# catbit.net
KiCad netlist of a schematic drawn in EAGLE
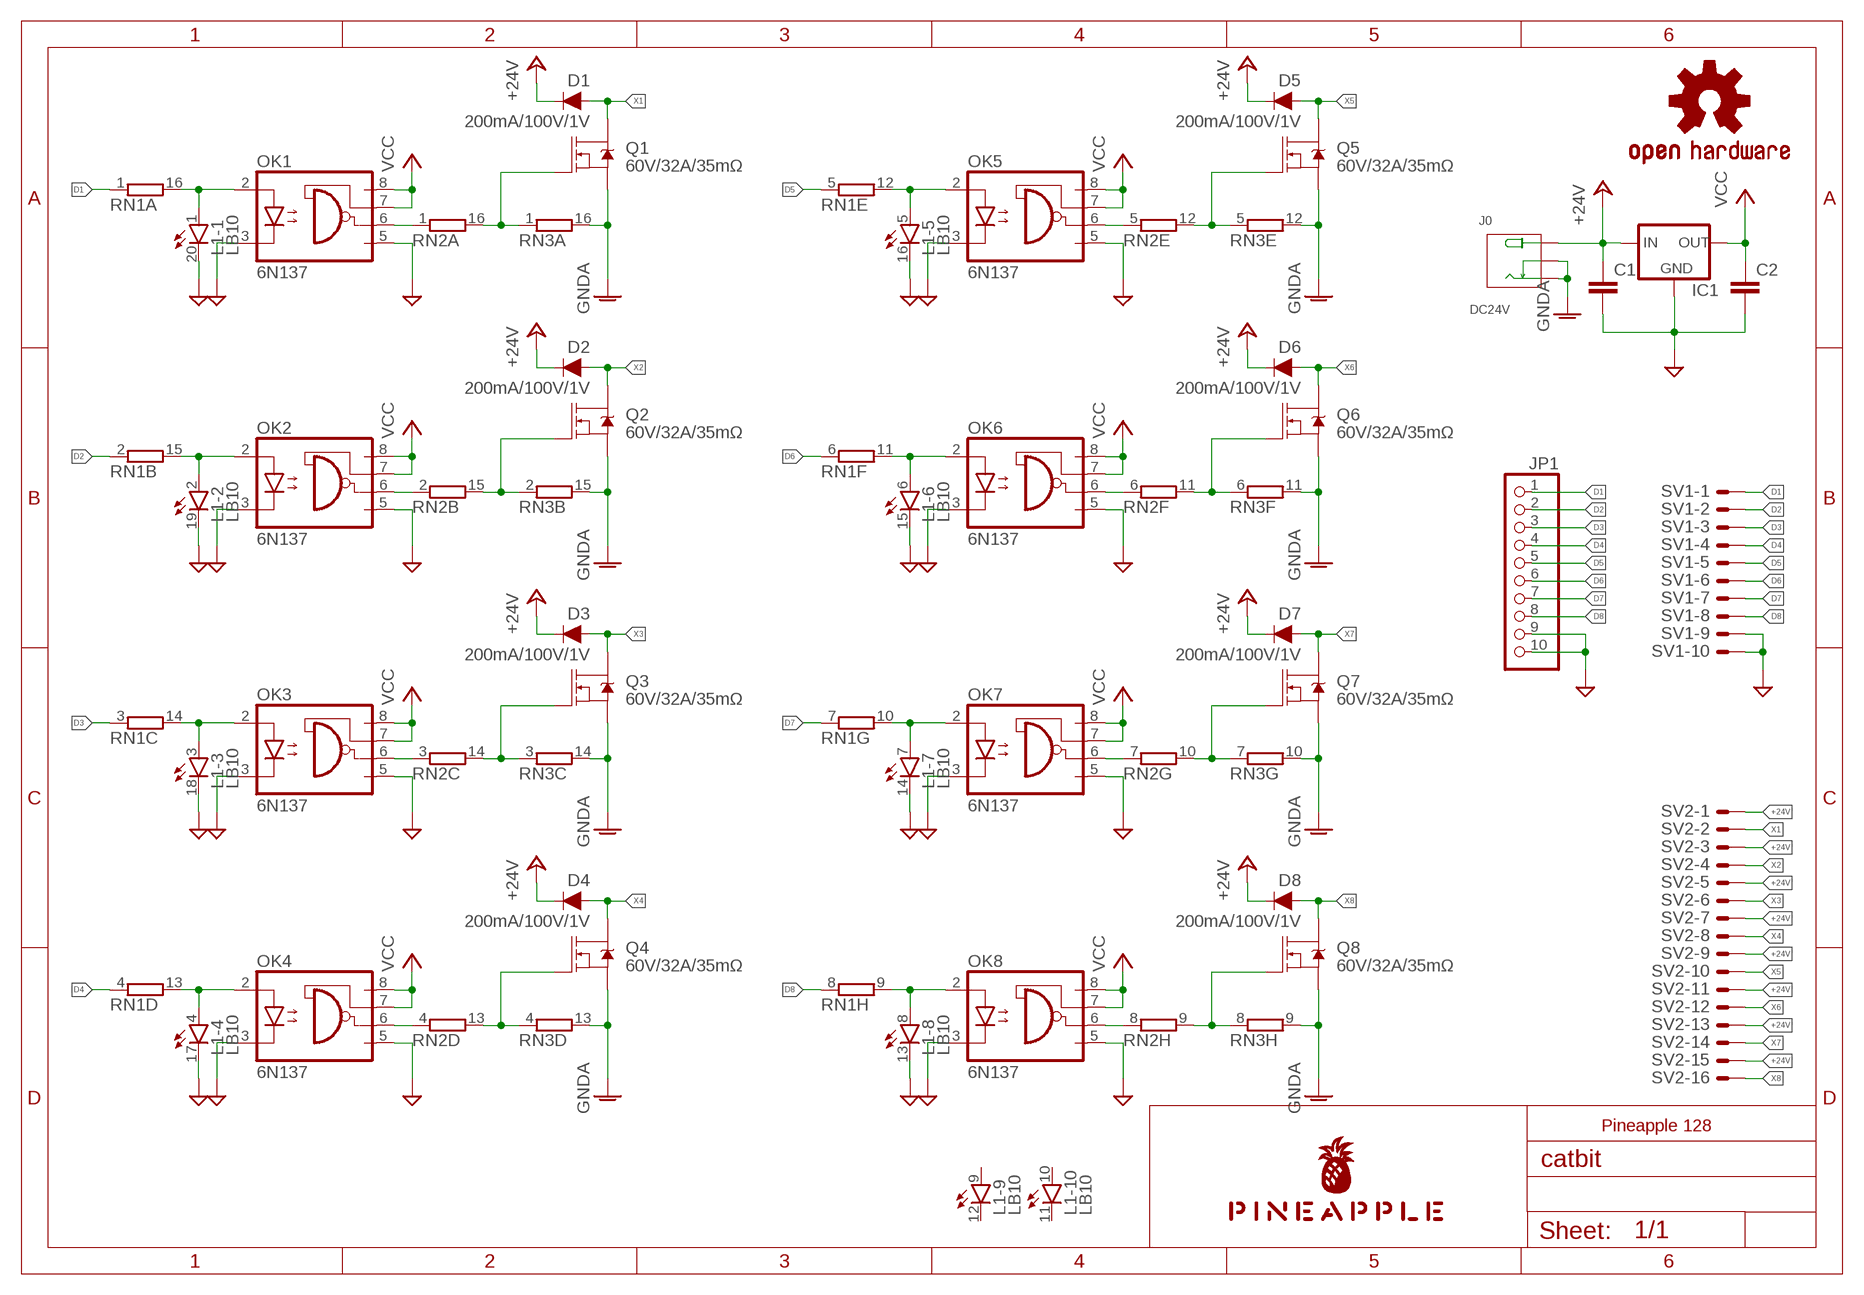
[diagram p0: schematic, sheet 1]

(export (version "E")
  (design (tool "Eeschema 10.0.6"))
  (components
    (comp (ref "C1")
      (value "C-EU025-024X044")
      (footprint "eagle-import:C025-024X044")
      (libsource (lib "eagle-import") (part "C-EU025-024X044"))
    )
    (comp (ref "C2")
      (value "C-EU025-024X044")
      (footprint "eagle-import:C025-024X044")
      (libsource (lib "eagle-import") (part "C-EU025-024X044"))
    )
    (comp (ref "D1")
      (value "200mA/100V/1V")
      (footprint "eagle-import:DIODE-1N4148")
      (libsource (lib "eagle-import") (part "DIODE-1N4148"))
    )
    (comp (ref "D2")
      (value "200mA/100V/1V")
      (footprint "eagle-import:DIODE-1N4148")
      (libsource (lib "eagle-import") (part "DIODE-1N4148"))
    )
    (comp (ref "D3")
      (value "200mA/100V/1V")
      (footprint "eagle-import:DIODE-1N4148")
      (libsource (lib "eagle-import") (part "DIODE-1N4148"))
    )
    (comp (ref "D4")
      (value "200mA/100V/1V")
      (footprint "eagle-import:DIODE-1N4148")
      (libsource (lib "eagle-import") (part "DIODE-1N4148"))
    )
    (comp (ref "D5")
      (value "200mA/100V/1V")
      (footprint "eagle-import:DIODE-1N4148")
      (libsource (lib "eagle-import") (part "DIODE-1N4148"))
    )
    (comp (ref "D6")
      (value "200mA/100V/1V")
      (footprint "eagle-import:DIODE-1N4148")
      (libsource (lib "eagle-import") (part "DIODE-1N4148"))
    )
    (comp (ref "D7")
      (value "200mA/100V/1V")
      (footprint "eagle-import:DIODE-1N4148")
      (libsource (lib "eagle-import") (part "DIODE-1N4148"))
    )
    (comp (ref "D8")
      (value "200mA/100V/1V")
      (footprint "eagle-import:DIODE-1N4148")
      (libsource (lib "eagle-import") (part "DIODE-1N4148"))
    )
    (comp (ref "IC1")
      (value "78XXS")
      (footprint "eagle-import:78XXS")
      (libsource (lib "eagle-import") (part "78XXS"))
    )
    (comp (ref "J0")
      (value "DC24V")
      (footprint "eagle-import:3P-L14.2_W11.0_H9.0MM")
      (libsource (lib "eagle-import") (part "JACK-DC-005'DC-005'"))
    )
    (comp (ref "JP1")
      (value "PINHD-1X10")
      (footprint "eagle-import:1X10")
      (libsource (lib "eagle-import") (part "PINHD-1X10"))
    )
    (comp (ref "L1")
      (value "LB10")
      (footprint "eagle-import:LB10")
      (libsource (lib "eagle-import") (part "LB10"))
    )
    (comp (ref "LOGO1")
      (value "OSHW-LOGOS-COPPER")
      (footprint "eagle-import:OSHW-LOGO-S_COPPER")
      (libsource (lib "eagle-import") (part "OSHW-LOGOS-COPPER"))
    )
    (comp (ref "OK1")
      (value "6N137")
      (footprint "eagle-import:DIL08")
      (libsource (lib "eagle-import") (part "6N137"))
    )
    (comp (ref "OK2")
      (value "6N137")
      (footprint "eagle-import:DIL08")
      (libsource (lib "eagle-import") (part "6N137"))
    )
    (comp (ref "OK3")
      (value "6N137")
      (footprint "eagle-import:DIL08")
      (libsource (lib "eagle-import") (part "6N137"))
    )
    (comp (ref "OK4")
      (value "6N137")
      (footprint "eagle-import:DIL08")
      (libsource (lib "eagle-import") (part "6N137"))
    )
    (comp (ref "OK5")
      (value "6N137")
      (footprint "eagle-import:DIL08")
      (libsource (lib "eagle-import") (part "6N137"))
    )
    (comp (ref "OK6")
      (value "6N137")
      (footprint "eagle-import:DIL08")
      (libsource (lib "eagle-import") (part "6N137"))
    )
    (comp (ref "OK7")
      (value "6N137")
      (footprint "eagle-import:DIL08")
      (libsource (lib "eagle-import") (part "6N137"))
    )
    (comp (ref "OK8")
      (value "6N137")
      (footprint "eagle-import:DIL08")
      (libsource (lib "eagle-import") (part "6N137"))
    )
    (comp (ref "Q1")
      (value "60V/32A/35mΩ")
      (footprint "eagle-import:TO220V")
      (libsource (lib "eagle-import") (part "MOSFET-NCH-FQP30N06L"))
    )
    (comp (ref "Q2")
      (value "60V/32A/35mΩ")
      (footprint "eagle-import:TO220V")
      (libsource (lib "eagle-import") (part "MOSFET-NCH-FQP30N06L"))
    )
    (comp (ref "Q3")
      (value "60V/32A/35mΩ")
      (footprint "eagle-import:TO220V")
      (libsource (lib "eagle-import") (part "MOSFET-NCH-FQP30N06L"))
    )
    (comp (ref "Q4")
      (value "60V/32A/35mΩ")
      (footprint "eagle-import:TO220V")
      (libsource (lib "eagle-import") (part "MOSFET-NCH-FQP30N06L"))
    )
    (comp (ref "Q5")
      (value "60V/32A/35mΩ")
      (footprint "eagle-import:TO220V")
      (libsource (lib "eagle-import") (part "MOSFET-NCH-FQP30N06L"))
    )
    (comp (ref "Q6")
      (value "60V/32A/35mΩ")
      (footprint "eagle-import:TO220V")
      (libsource (lib "eagle-import") (part "MOSFET-NCH-FQP30N06L"))
    )
    (comp (ref "Q7")
      (value "60V/32A/35mΩ")
      (footprint "eagle-import:TO220V")
      (libsource (lib "eagle-import") (part "MOSFET-NCH-FQP30N06L"))
    )
    (comp (ref "Q8")
      (value "60V/32A/35mΩ")
      (footprint "eagle-import:TO220V")
      (libsource (lib "eagle-import") (part "MOSFET-NCH-FQP30N06L"))
    )
    (comp (ref "RN1")
      (value "8R-N")
      (footprint "eagle-import:DIL16")
      (libsource (lib "eagle-import") (part "8R-N"))
    )
    (comp (ref "RN2")
      (value "8R-N")
      (footprint "eagle-import:DIL16")
      (libsource (lib "eagle-import") (part "8R-N"))
    )
    (comp (ref "RN3")
      (value "8R-N")
      (footprint "eagle-import:DIL16")
      (libsource (lib "eagle-import") (part "8R-N"))
    )
    (comp (ref "SV1")
      (value "ML10LE")
      (footprint "eagle-import:ML10L")
      (libsource (lib "eagle-import") (part "ML10LE"))
    )
    (comp (ref "SV2")
      (value "ML16LE")
      (footprint "eagle-import:ML16L")
      (libsource (lib "eagle-import") (part "ML16LE"))
    )
    (comp (ref "U$1")
      (value "PINEAPPLE450_SILK")
      (footprint "eagle-import:PINEAPPLE450_SILK")
      (libsource (lib "eagle-import") (part "PINEAPPLE450_SILK"))
    )
  )
  (nets
    (net (code "1") (name "+24V") (class "Default")
      (node (ref "C1") (pin "1") (pinfunction "1_1") (pintype "passive"))
      (node (ref "D1") (pin "C") (pinfunction "C_C") (pintype "passive"))
      (node (ref "D2") (pin "C") (pinfunction "C_C") (pintype "passive"))
      (node (ref "D3") (pin "C") (pinfunction "C_C") (pintype "passive"))
      (node (ref "D4") (pin "C") (pinfunction "C_C") (pintype "passive"))
      (node (ref "D5") (pin "C") (pinfunction "C_C") (pintype "passive"))
      (node (ref "D6") (pin "C") (pinfunction "C_C") (pintype "passive"))
      (node (ref "D7") (pin "C") (pinfunction "C_C") (pintype "passive"))
      (node (ref "D8") (pin "C") (pinfunction "C_C") (pintype "passive"))
      (node (ref "IC1") (pin "IN") (pinfunction "IN_IN") (pintype "input"))
      (node (ref "J0") (pin "+") (pinfunction "+_+") (pintype "bidirectional"))
      (node (ref "SV2") (pin "1") (pinfunction "S_1") (pintype "passive"))
      (node (ref "SV2") (pin "11") (pinfunction "S_11") (pintype "passive"))
      (node (ref "SV2") (pin "13") (pinfunction "S_13") (pintype "passive"))
      (node (ref "SV2") (pin "15") (pinfunction "S_15") (pintype "passive"))
      (node (ref "SV2") (pin "3") (pinfunction "S_3") (pintype "passive"))
      (node (ref "SV2") (pin "5") (pinfunction "S_5") (pintype "passive"))
      (node (ref "SV2") (pin "7") (pinfunction "S_7") (pintype "passive"))
      (node (ref "SV2") (pin "9") (pinfunction "S_9") (pintype "passive"))
    )
    (net (code "2") (name "D1") (class "Default")
      (node (ref "JP1") (pin "1") (pinfunction "1_1") (pintype "passive"))
      (node (ref "RN1") (pin "1") (pinfunction "1_1") (pintype "passive"))
      (node (ref "SV1") (pin "1") (pinfunction "S_1") (pintype "passive"))
    )
    (net (code "3") (name "D2") (class "Default")
      (node (ref "JP1") (pin "2") (pinfunction "2_2") (pintype "passive"))
      (node (ref "RN1") (pin "2") (pinfunction "1_2") (pintype "passive"))
      (node (ref "SV1") (pin "2") (pinfunction "S_2") (pintype "passive"))
    )
    (net (code "4") (name "D3") (class "Default")
      (node (ref "JP1") (pin "3") (pinfunction "3_3") (pintype "passive"))
      (node (ref "RN1") (pin "3") (pinfunction "1_3") (pintype "passive"))
      (node (ref "SV1") (pin "3") (pinfunction "S_3") (pintype "passive"))
    )
    (net (code "5") (name "D4") (class "Default")
      (node (ref "JP1") (pin "4") (pinfunction "4_4") (pintype "passive"))
      (node (ref "RN1") (pin "4") (pinfunction "1_4") (pintype "passive"))
      (node (ref "SV1") (pin "4") (pinfunction "S_4") (pintype "passive"))
    )
    (net (code "6") (name "D5") (class "Default")
      (node (ref "JP1") (pin "5") (pinfunction "5_5") (pintype "passive"))
      (node (ref "RN1") (pin "5") (pinfunction "1_5") (pintype "passive"))
      (node (ref "SV1") (pin "5") (pinfunction "S_5") (pintype "passive"))
    )
    (net (code "7") (name "D6") (class "Default")
      (node (ref "JP1") (pin "6") (pinfunction "6_6") (pintype "passive"))
      (node (ref "RN1") (pin "6") (pinfunction "1_6") (pintype "passive"))
      (node (ref "SV1") (pin "6") (pinfunction "S_6") (pintype "passive"))
    )
    (net (code "8") (name "D7") (class "Default")
      (node (ref "JP1") (pin "7") (pinfunction "7_7") (pintype "passive"))
      (node (ref "RN1") (pin "7") (pinfunction "1_7") (pintype "passive"))
      (node (ref "SV1") (pin "7") (pinfunction "S_7") (pintype "passive"))
    )
    (net (code "9") (name "D8") (class "Default")
      (node (ref "JP1") (pin "8") (pinfunction "8_8") (pintype "passive"))
      (node (ref "RN1") (pin "8") (pinfunction "1_8") (pintype "passive"))
      (node (ref "SV1") (pin "8") (pinfunction "S_8") (pintype "passive"))
    )
    (net (code "10") (name "GND") (class "Default")
      (node (ref "C1") (pin "2") (pinfunction "2_2") (pintype "passive"))
      (node (ref "C2") (pin "2") (pinfunction "2_2") (pintype "passive"))
      (node (ref "IC1") (pin "GND") (pinfunction "GND_GND") (pintype "input"))
      (node (ref "JP1") (pin "10") (pinfunction "10_10") (pintype "passive"))
      (node (ref "JP1") (pin "9") (pinfunction "9_9") (pintype "passive"))
      (node (ref "L1") (pin "13") (pinfunction "C_13") (pintype "passive"))
      (node (ref "L1") (pin "14") (pinfunction "C_14") (pintype "passive"))
      (node (ref "L1") (pin "15") (pinfunction "C_15") (pintype "passive"))
      (node (ref "L1") (pin "16") (pinfunction "C_16") (pintype "passive"))
      (node (ref "L1") (pin "17") (pinfunction "C_17") (pintype "passive"))
      (node (ref "L1") (pin "18") (pinfunction "C_18") (pintype "passive"))
      (node (ref "L1") (pin "19") (pinfunction "C_19") (pintype "passive"))
      (node (ref "L1") (pin "20") (pinfunction "C_20") (pintype "passive"))
      (node (ref "OK1") (pin "3") (pinfunction "C_3") (pintype "passive"))
      (node (ref "OK1") (pin "5") (pinfunction "GND_5") (pintype "passive"))
      (node (ref "OK2") (pin "3") (pinfunction "C_3") (pintype "passive"))
      (node (ref "OK2") (pin "5") (pinfunction "GND_5") (pintype "passive"))
      (node (ref "OK3") (pin "3") (pinfunction "C_3") (pintype "passive"))
      (node (ref "OK3") (pin "5") (pinfunction "GND_5") (pintype "passive"))
      (node (ref "OK4") (pin "3") (pinfunction "C_3") (pintype "passive"))
      (node (ref "OK4") (pin "5") (pinfunction "GND_5") (pintype "passive"))
      (node (ref "OK5") (pin "3") (pinfunction "C_3") (pintype "passive"))
      (node (ref "OK5") (pin "5") (pinfunction "GND_5") (pintype "passive"))
      (node (ref "OK6") (pin "3") (pinfunction "C_3") (pintype "passive"))
      (node (ref "OK6") (pin "5") (pinfunction "GND_5") (pintype "passive"))
      (node (ref "OK7") (pin "3") (pinfunction "C_3") (pintype "passive"))
      (node (ref "OK7") (pin "5") (pinfunction "GND_5") (pintype "passive"))
      (node (ref "OK8") (pin "3") (pinfunction "C_3") (pintype "passive"))
      (node (ref "OK8") (pin "5") (pinfunction "GND_5") (pintype "passive"))
      (node (ref "SV1") (pin "10") (pinfunction "S_10") (pintype "passive"))
      (node (ref "SV1") (pin "9") (pinfunction "S_9") (pintype "passive"))
    )
    (net (code "11") (name "GNDA") (class "Default")
      (node (ref "J0") (pin "-1") (pinfunction "-_-1") (pintype "bidirectional"))
      (node (ref "J0") (pin "-2") (pinfunction "CDN_-2") (pintype "bidirectional"))
      (node (ref "Q1") (pin "3") (pinfunction "S_3") (pintype "bidirectional"))
      (node (ref "Q2") (pin "3") (pinfunction "S_3") (pintype "bidirectional"))
      (node (ref "Q3") (pin "3") (pinfunction "S_3") (pintype "bidirectional"))
      (node (ref "Q4") (pin "3") (pinfunction "S_3") (pintype "bidirectional"))
      (node (ref "Q5") (pin "3") (pinfunction "S_3") (pintype "bidirectional"))
      (node (ref "Q6") (pin "3") (pinfunction "S_3") (pintype "bidirectional"))
      (node (ref "Q7") (pin "3") (pinfunction "S_3") (pintype "bidirectional"))
      (node (ref "Q8") (pin "3") (pinfunction "S_3") (pintype "bidirectional"))
      (node (ref "RN3") (pin "10") (pinfunction "2_10") (pintype "passive"))
      (node (ref "RN3") (pin "11") (pinfunction "2_11") (pintype "passive"))
      (node (ref "RN3") (pin "12") (pinfunction "2_12") (pintype "passive"))
      (node (ref "RN3") (pin "13") (pinfunction "2_13") (pintype "passive"))
      (node (ref "RN3") (pin "14") (pinfunction "2_14") (pintype "passive"))
      (node (ref "RN3") (pin "15") (pinfunction "2_15") (pintype "passive"))
      (node (ref "RN3") (pin "16") (pinfunction "2_16") (pintype "passive"))
      (node (ref "RN3") (pin "9") (pinfunction "2_9") (pintype "passive"))
    )
    (net (code "12") (name "Net-(L1A-A)") (class "Default")
      (node (ref "L1") (pin "1") (pinfunction "A_1") (pintype "passive"))
      (node (ref "OK1") (pin "2") (pinfunction "A_2") (pintype "passive"))
      (node (ref "RN1") (pin "16") (pinfunction "2_16") (pintype "passive"))
    )
    (net (code "13") (name "Net-(L1C-A)") (class "Default")
      (node (ref "L1") (pin "2") (pinfunction "A_2") (pintype "passive"))
      (node (ref "OK2") (pin "2") (pinfunction "A_2") (pintype "passive"))
      (node (ref "RN1") (pin "15") (pinfunction "2_15") (pintype "passive"))
    )
    (net (code "14") (name "Net-(L1D-A)") (class "Default")
      (node (ref "L1") (pin "3") (pinfunction "A_3") (pintype "passive"))
      (node (ref "OK3") (pin "2") (pinfunction "A_2") (pintype "passive"))
      (node (ref "RN1") (pin "14") (pinfunction "2_14") (pintype "passive"))
    )
    (net (code "15") (name "Net-(L1E-A)") (class "Default")
      (node (ref "L1") (pin "4") (pinfunction "A_4") (pintype "passive"))
      (node (ref "OK4") (pin "2") (pinfunction "A_2") (pintype "passive"))
      (node (ref "RN1") (pin "13") (pinfunction "2_13") (pintype "passive"))
    )
    (net (code "16") (name "Net-(L1F-A)") (class "Default")
      (node (ref "L1") (pin "5") (pinfunction "A_5") (pintype "passive"))
      (node (ref "OK5") (pin "2") (pinfunction "A_2") (pintype "passive"))
      (node (ref "RN1") (pin "12") (pinfunction "2_12") (pintype "passive"))
    )
    (net (code "17") (name "Net-(L1G-A)") (class "Default")
      (node (ref "L1") (pin "6") (pinfunction "A_6") (pintype "passive"))
      (node (ref "OK6") (pin "2") (pinfunction "A_2") (pintype "passive"))
      (node (ref "RN1") (pin "11") (pinfunction "2_11") (pintype "passive"))
    )
    (net (code "18") (name "Net-(L1H-A)") (class "Default")
      (node (ref "L1") (pin "7") (pinfunction "A_7") (pintype "passive"))
      (node (ref "OK7") (pin "2") (pinfunction "A_2") (pintype "passive"))
      (node (ref "RN1") (pin "10") (pinfunction "2_10") (pintype "passive"))
    )
    (net (code "19") (name "Net-(L1I-A)") (class "Default")
      (node (ref "L1") (pin "8") (pinfunction "A_8") (pintype "passive"))
      (node (ref "OK8") (pin "2") (pinfunction "A_2") (pintype "passive"))
      (node (ref "RN1") (pin "9") (pinfunction "2_9") (pintype "passive"))
    )
    (net (code "20") (name "Net-(OK1-VO)") (class "Default")
      (node (ref "OK1") (pin "6") (pinfunction "VO_6") (pintype "passive"))
      (node (ref "RN2") (pin "1") (pinfunction "1_1") (pintype "passive"))
    )
    (net (code "21") (name "Net-(OK2-VO)") (class "Default")
      (node (ref "OK2") (pin "6") (pinfunction "VO_6") (pintype "passive"))
      (node (ref "RN2") (pin "2") (pinfunction "1_2") (pintype "passive"))
    )
    (net (code "22") (name "Net-(OK3-VO)") (class "Default")
      (node (ref "OK3") (pin "6") (pinfunction "VO_6") (pintype "passive"))
      (node (ref "RN2") (pin "3") (pinfunction "1_3") (pintype "passive"))
    )
    (net (code "23") (name "Net-(OK4-VO)") (class "Default")
      (node (ref "OK4") (pin "6") (pinfunction "VO_6") (pintype "passive"))
      (node (ref "RN2") (pin "4") (pinfunction "1_4") (pintype "passive"))
    )
    (net (code "24") (name "Net-(OK5-VO)") (class "Default")
      (node (ref "OK5") (pin "6") (pinfunction "VO_6") (pintype "passive"))
      (node (ref "RN2") (pin "5") (pinfunction "1_5") (pintype "passive"))
    )
    (net (code "25") (name "Net-(OK6-VO)") (class "Default")
      (node (ref "OK6") (pin "6") (pinfunction "VO_6") (pintype "passive"))
      (node (ref "RN2") (pin "6") (pinfunction "1_6") (pintype "passive"))
    )
    (net (code "26") (name "Net-(OK7-VO)") (class "Default")
      (node (ref "OK7") (pin "6") (pinfunction "VO_6") (pintype "passive"))
      (node (ref "RN2") (pin "7") (pinfunction "1_7") (pintype "passive"))
    )
    (net (code "27") (name "Net-(OK8-VO)") (class "Default")
      (node (ref "OK8") (pin "6") (pinfunction "VO_6") (pintype "passive"))
      (node (ref "RN2") (pin "8") (pinfunction "1_8") (pintype "passive"))
    )
    (net (code "28") (name "Net-(Q1-G)") (class "Default")
      (node (ref "Q1") (pin "1") (pinfunction "G_1") (pintype "bidirectional"))
      (node (ref "RN2") (pin "16") (pinfunction "2_16") (pintype "passive"))
      (node (ref "RN3") (pin "1") (pinfunction "1_1") (pintype "passive"))
    )
    (net (code "29") (name "Net-(Q2-G)") (class "Default")
      (node (ref "Q2") (pin "1") (pinfunction "G_1") (pintype "bidirectional"))
      (node (ref "RN2") (pin "15") (pinfunction "2_15") (pintype "passive"))
      (node (ref "RN3") (pin "2") (pinfunction "1_2") (pintype "passive"))
    )
    (net (code "30") (name "Net-(Q3-G)") (class "Default")
      (node (ref "Q3") (pin "1") (pinfunction "G_1") (pintype "bidirectional"))
      (node (ref "RN2") (pin "14") (pinfunction "2_14") (pintype "passive"))
      (node (ref "RN3") (pin "3") (pinfunction "1_3") (pintype "passive"))
    )
    (net (code "31") (name "Net-(Q4-G)") (class "Default")
      (node (ref "Q4") (pin "1") (pinfunction "G_1") (pintype "bidirectional"))
      (node (ref "RN2") (pin "13") (pinfunction "2_13") (pintype "passive"))
      (node (ref "RN3") (pin "4") (pinfunction "1_4") (pintype "passive"))
    )
    (net (code "32") (name "Net-(Q5-G)") (class "Default")
      (node (ref "Q5") (pin "1") (pinfunction "G_1") (pintype "bidirectional"))
      (node (ref "RN2") (pin "12") (pinfunction "2_12") (pintype "passive"))
      (node (ref "RN3") (pin "5") (pinfunction "1_5") (pintype "passive"))
    )
    (net (code "33") (name "Net-(Q6-G)") (class "Default")
      (node (ref "Q6") (pin "1") (pinfunction "G_1") (pintype "bidirectional"))
      (node (ref "RN2") (pin "11") (pinfunction "2_11") (pintype "passive"))
      (node (ref "RN3") (pin "6") (pinfunction "1_6") (pintype "passive"))
    )
    (net (code "34") (name "Net-(Q7-G)") (class "Default")
      (node (ref "Q7") (pin "1") (pinfunction "G_1") (pintype "bidirectional"))
      (node (ref "RN2") (pin "10") (pinfunction "2_10") (pintype "passive"))
      (node (ref "RN3") (pin "7") (pinfunction "1_7") (pintype "passive"))
    )
    (net (code "35") (name "Net-(Q8-G)") (class "Default")
      (node (ref "Q8") (pin "1") (pinfunction "G_1") (pintype "bidirectional"))
      (node (ref "RN2") (pin "9") (pinfunction "2_9") (pintype "passive"))
      (node (ref "RN3") (pin "8") (pinfunction "1_8") (pintype "passive"))
    )
    (net (code "36") (name "VCC") (class "Default")
      (node (ref "C2") (pin "1") (pinfunction "1_1") (pintype "passive"))
      (node (ref "IC1") (pin "OUT") (pinfunction "OUT_OUT") (pintype "passive"))
      (node (ref "OK1") (pin "7") (pinfunction "VE_7") (pintype "passive"))
      (node (ref "OK1") (pin "8") (pinfunction "VCC_8") (pintype "passive"))
      (node (ref "OK2") (pin "7") (pinfunction "VE_7") (pintype "passive"))
      (node (ref "OK2") (pin "8") (pinfunction "VCC_8") (pintype "passive"))
      (node (ref "OK3") (pin "7") (pinfunction "VE_7") (pintype "passive"))
      (node (ref "OK3") (pin "8") (pinfunction "VCC_8") (pintype "passive"))
      (node (ref "OK4") (pin "7") (pinfunction "VE_7") (pintype "passive"))
      (node (ref "OK4") (pin "8") (pinfunction "VCC_8") (pintype "passive"))
      (node (ref "OK5") (pin "7") (pinfunction "VE_7") (pintype "passive"))
      (node (ref "OK5") (pin "8") (pinfunction "VCC_8") (pintype "passive"))
      (node (ref "OK6") (pin "7") (pinfunction "VE_7") (pintype "passive"))
      (node (ref "OK6") (pin "8") (pinfunction "VCC_8") (pintype "passive"))
      (node (ref "OK7") (pin "7") (pinfunction "VE_7") (pintype "passive"))
      (node (ref "OK7") (pin "8") (pinfunction "VCC_8") (pintype "passive"))
      (node (ref "OK8") (pin "7") (pinfunction "VE_7") (pintype "passive"))
      (node (ref "OK8") (pin "8") (pinfunction "VCC_8") (pintype "passive"))
    )
    (net (code "37") (name "X1") (class "Default")
      (node (ref "D1") (pin "A") (pinfunction "A_A") (pintype "passive"))
      (node (ref "Q1") (pin "2") (pinfunction "D_2") (pintype "bidirectional"))
      (node (ref "SV2") (pin "2") (pinfunction "S_2") (pintype "passive"))
    )
    (net (code "38") (name "X2") (class "Default")
      (node (ref "D2") (pin "A") (pinfunction "A_A") (pintype "passive"))
      (node (ref "Q2") (pin "2") (pinfunction "D_2") (pintype "bidirectional"))
      (node (ref "SV2") (pin "4") (pinfunction "S_4") (pintype "passive"))
    )
    (net (code "39") (name "X3") (class "Default")
      (node (ref "D3") (pin "A") (pinfunction "A_A") (pintype "passive"))
      (node (ref "Q3") (pin "2") (pinfunction "D_2") (pintype "bidirectional"))
      (node (ref "SV2") (pin "6") (pinfunction "S_6") (pintype "passive"))
    )
    (net (code "40") (name "X4") (class "Default")
      (node (ref "D4") (pin "A") (pinfunction "A_A") (pintype "passive"))
      (node (ref "Q4") (pin "2") (pinfunction "D_2") (pintype "bidirectional"))
      (node (ref "SV2") (pin "8") (pinfunction "S_8") (pintype "passive"))
    )
    (net (code "41") (name "X5") (class "Default")
      (node (ref "D5") (pin "A") (pinfunction "A_A") (pintype "passive"))
      (node (ref "Q5") (pin "2") (pinfunction "D_2") (pintype "bidirectional"))
      (node (ref "SV2") (pin "10") (pinfunction "S_10") (pintype "passive"))
    )
    (net (code "42") (name "X6") (class "Default")
      (node (ref "D6") (pin "A") (pinfunction "A_A") (pintype "passive"))
      (node (ref "Q6") (pin "2") (pinfunction "D_2") (pintype "bidirectional"))
      (node (ref "SV2") (pin "12") (pinfunction "S_12") (pintype "passive"))
    )
    (net (code "43") (name "X7") (class "Default")
      (node (ref "D7") (pin "A") (pinfunction "A_A") (pintype "passive"))
      (node (ref "Q7") (pin "2") (pinfunction "D_2") (pintype "bidirectional"))
      (node (ref "SV2") (pin "14") (pinfunction "S_14") (pintype "passive"))
    )
    (net (code "44") (name "X8") (class "Default")
      (node (ref "D8") (pin "A") (pinfunction "A_A") (pintype "passive"))
      (node (ref "Q8") (pin "2") (pinfunction "D_2") (pintype "bidirectional"))
      (node (ref "SV2") (pin "16") (pinfunction "S_16") (pintype "passive"))
    )
    (net (code "45") (name "unconnected-(L1B-A-Pad10)") (class "Default")
      (node (ref "L1") (pin "10") (pinfunction "A_10") (pintype "passive"))
    )
    (net (code "46") (name "unconnected-(L1B-C-Pad11)") (class "Default")
      (node (ref "L1") (pin "11") (pinfunction "C_11") (pintype "passive"))
    )
    (net (code "47") (name "unconnected-(L1J-A-Pad9)") (class "Default")
      (node (ref "L1") (pin "9") (pinfunction "A_9") (pintype "passive"))
    )
    (net (code "48") (name "unconnected-(L1J-C-Pad12)") (class "Default")
      (node (ref "L1") (pin "12") (pinfunction "C_12") (pintype "passive"))
    )
  )
)
